# 1.net
KiCad netlist of a schematic drawn in Altium Designer
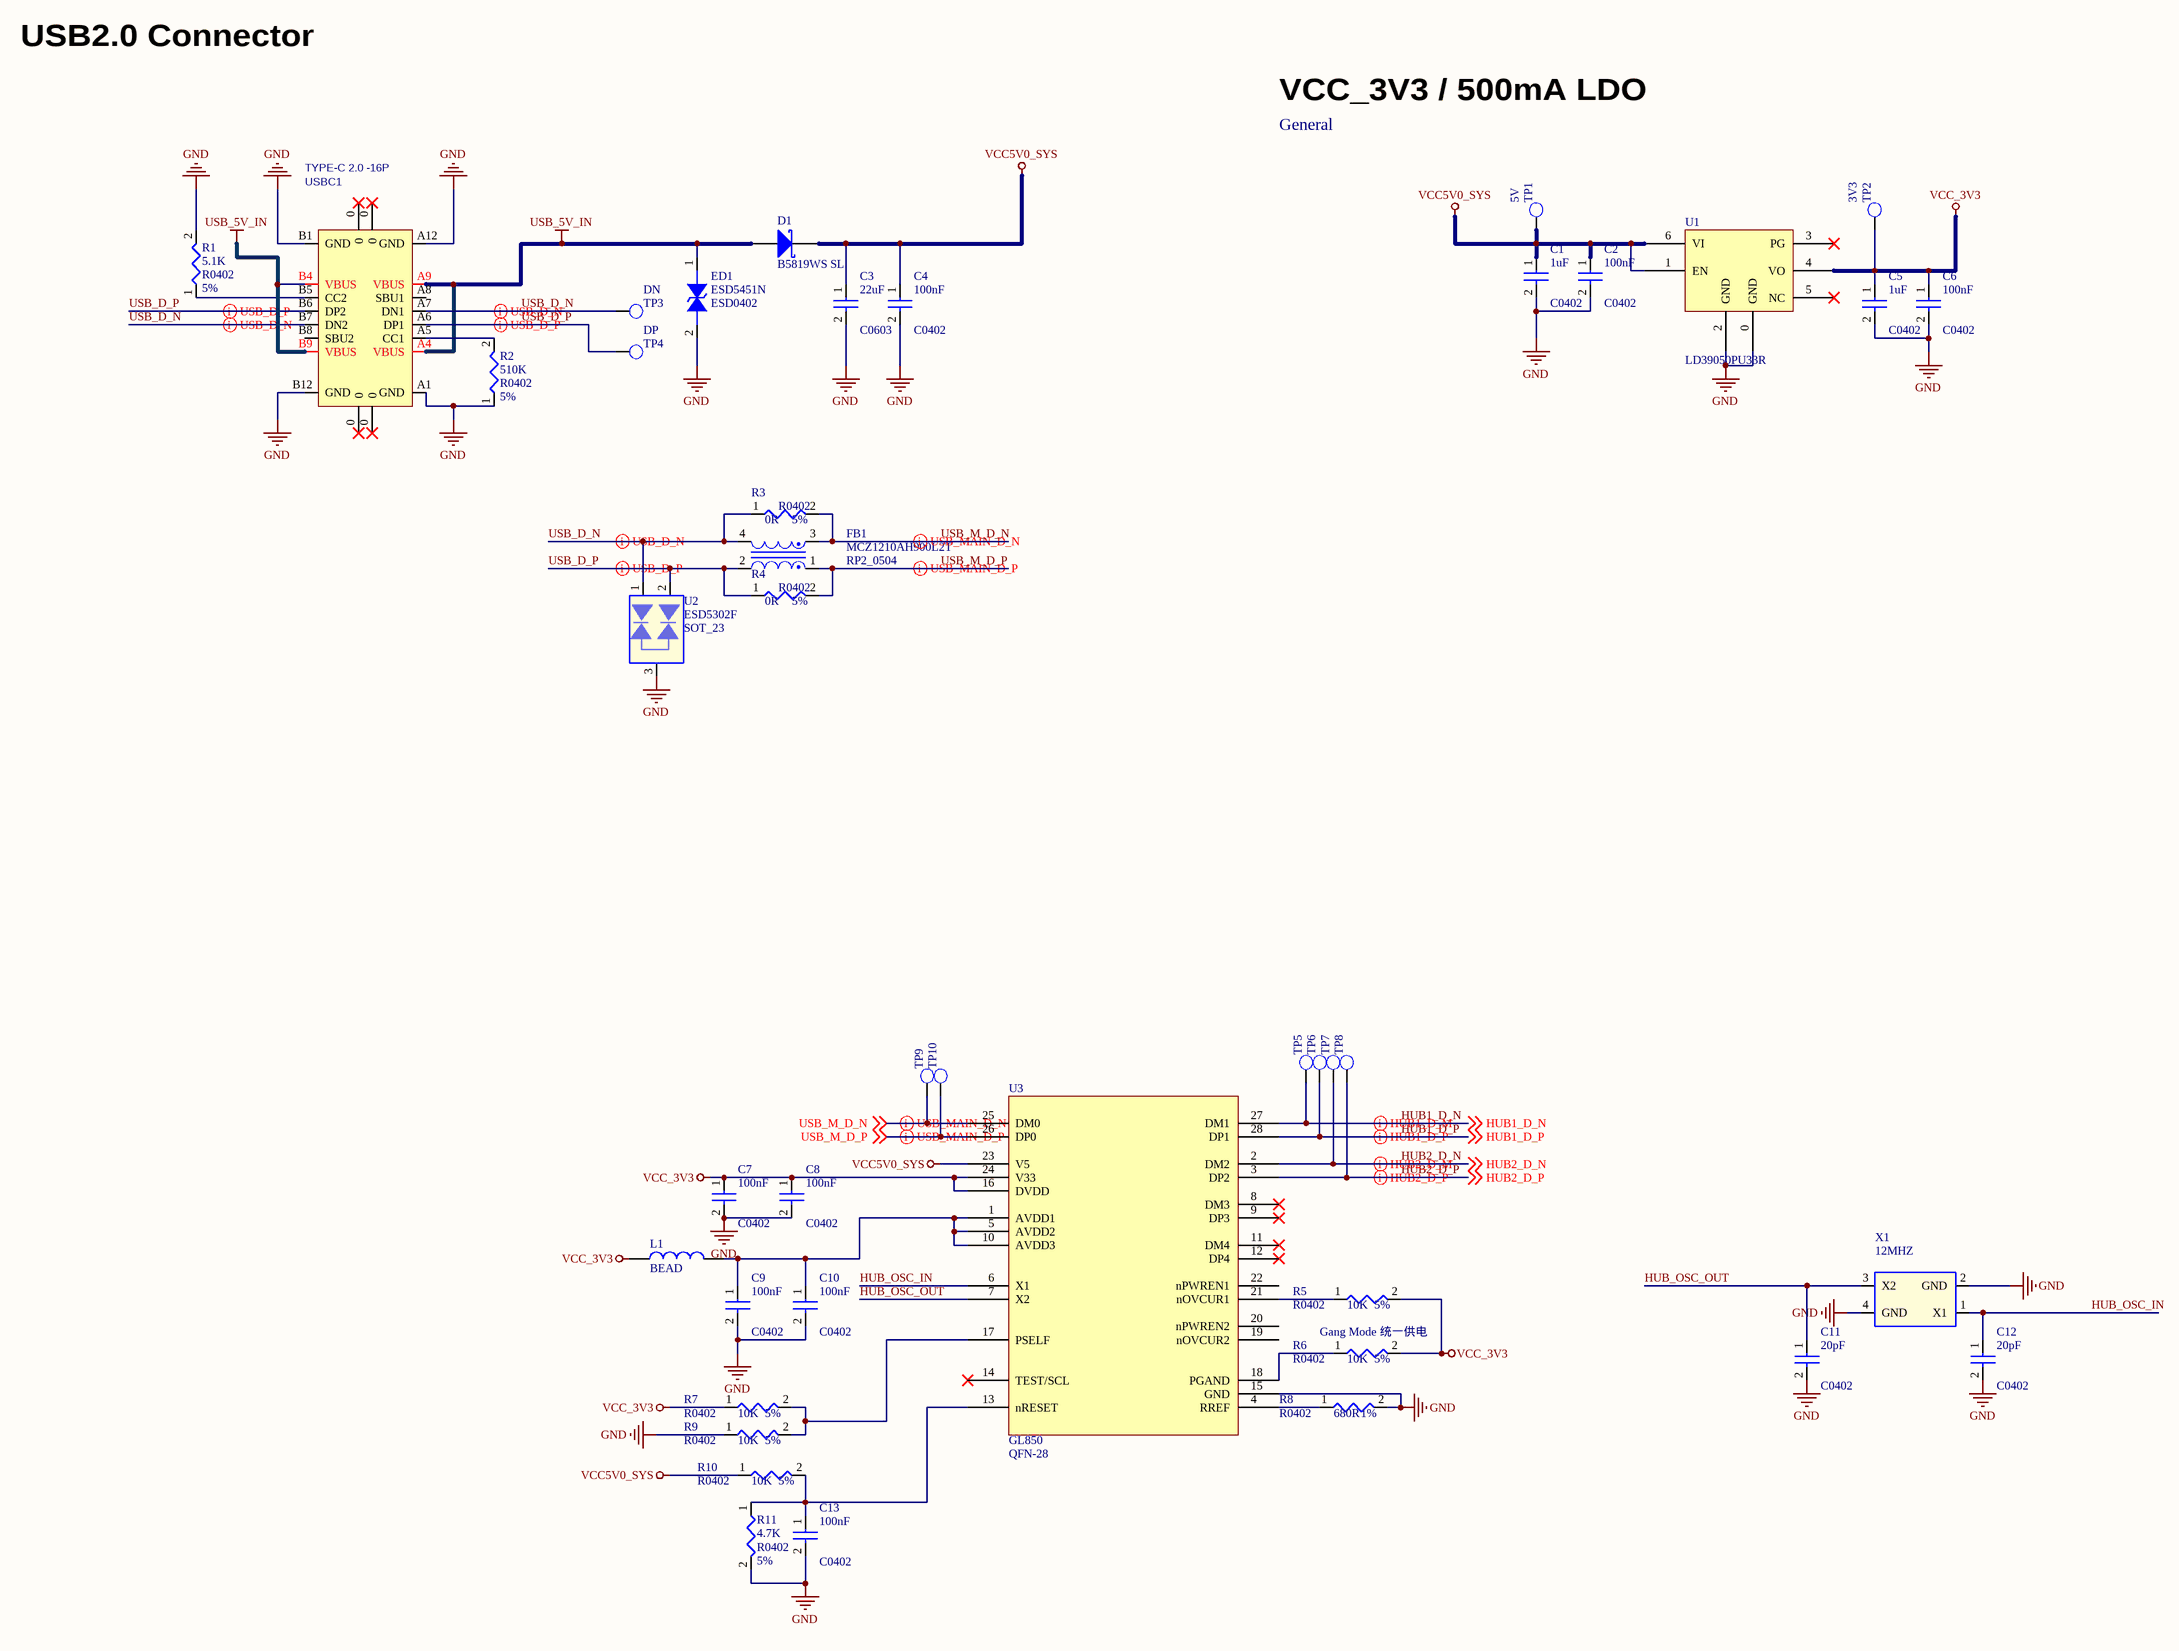
[diagram p0: 1.SchDoc]

(export (version "E")
  (design (tool "Eeschema 10.0.6"))
  (components
    (comp (ref "C1")
      (value "1uF")
      (footprint "C0402_L")
      (description "cap,1.0uF,+/-10%,6.3V,X5R,C0402")
      (fields (field (name "PCB FOOTPRINT") "C0402") (field (name "MANUFACTURER_PART_NUMBER") "Open/Any"))
      (libsource (lib "*") (part "CAP NP_Dup1"))
    )
    (comp (ref "C2")
      (value "100nF")
      (footprint "C0402_L")
      (description "cap,1.0uF,+/-10%,6.3V,C0402")
      (fields (field (name "PCB FOOTPRINT") "C0402") (field (name "MANUFACTURER_PART_NUMBER") "Open/Any"))
      (libsource (lib "*") (part "CAP NP_Dup1"))
    )
    (comp (ref "C3")
      (value "22uF")
      (footprint "C0603_L")
      (description "cap,22.00uF,+/-10%,10V,X5R,C0603")
      (fields (field (name "PCB FOOTPRINT") "C0603") (field (name "MANUFACTURER_PART_NUMBER") "Open/Any"))
      (libsource (lib "*") (part "CAP NP_Dup1"))
    )
    (comp (ref "C4")
      (value "100nF")
      (footprint "C0402_L")
      (description "cap,100.00nF,+/-10%,10V,X5R,C0402")
      (fields (field (name "PCB FOOTPRINT") "C0402") (field (name "MANUFACTURER_PART_NUMBER") "Open/Any"))
      (libsource (lib "*") (part "CAP NP_Dup1"))
    )
    (comp (ref "C5")
      (value "1uF")
      (footprint "C0402_L")
      (description "cap,1.0uF,+/-10%,6.3V,X5R,C0402")
      (fields (field (name "PCB FOOTPRINT") "C0402") (field (name "MANUFACTURER_PART_NUMBER") "Open/Any"))
      (libsource (lib "*") (part "CAP NP_Dup1"))
    )
    (comp (ref "C6")
      (value "100nF")
      (footprint "C0402_L")
      (description "cap,1.0uF,+/-10%,6.3V,C0402")
      (fields (field (name "PCB FOOTPRINT") "C0402") (field (name "MANUFACTURER_PART_NUMBER") "Open/Any"))
      (libsource (lib "*") (part "CAP NP_Dup1"))
    )
    (comp (ref "C7")
      (value "100nF")
      (footprint "C0402_L")
      (description "cap,100.00nF,+/-10%,10V,X5R,C0402")
      (fields (field (name "PCB FOOTPRINT") "C0402") (field (name "MANUFACTURER_PART_NUMBER") "Open/Any"))
      (libsource (lib "*") (part "CAP NP_Dup1"))
    )
    (comp (ref "C8")
      (value "100nF")
      (footprint "C0402_L")
      (description "cap,100.00nF,+/-10%,10V,X5R,C0402")
      (fields (field (name "PCB FOOTPRINT") "C0402") (field (name "MANUFACTURER_PART_NUMBER") "Open/Any"))
      (libsource (lib "*") (part "CAP NP_Dup1"))
    )
    (comp (ref "C9")
      (value "100nF")
      (footprint "C0402_L")
      (description "cap,100.00nF,+/-10%,10V,X5R,C0402")
      (fields (field (name "PCB FOOTPRINT") "C0402") (field (name "MANUFACTURER_PART_NUMBER") "Open/Any"))
      (libsource (lib "*") (part "CAP NP_Dup1"))
    )
    (comp (ref "C10")
      (value "100nF")
      (footprint "C0402_L")
      (description "cap,100.00nF,+/-10%,10V,X5R,C0402")
      (fields (field (name "PCB FOOTPRINT") "C0402") (field (name "MANUFACTURER_PART_NUMBER") "Open/Any"))
      (libsource (lib "*") (part "CAP NP_Dup1"))
    )
    (comp (ref "C11")
      (value "20pF")
      (footprint "C0402_L")
      (description "cap,20pF,+/-10%,25V,X5R,C0402")
      (fields (field (name "PCB FOOTPRINT") "C0402") (field (name "MANUFACTURER_PART_NUMBER") "Open/Any"))
      (libsource (lib "*") (part "CAP NP_Dup1"))
    )
    (comp (ref "C12")
      (value "20pF")
      (footprint "C0402_L")
      (description "cap,20pF,+/-10%,25V,X5R,C0402")
      (fields (field (name "PCB FOOTPRINT") "C0402") (field (name "MANUFACTURER_PART_NUMBER") "Open/Any"))
      (libsource (lib "*") (part "CAP NP_Dup1"))
    )
    (comp (ref "C13")
      (value "100nF")
      (footprint "C0402_L")
      (description "cap,100.00nF,+/-10%,10V,X5R,C0402")
      (fields (field (name "PCB FOOTPRINT") "C0402") (field (name "MANUFACTURER_PART_NUMBER") "Open/Any"))
      (libsource (lib "*") (part "CAP NP_Dup1"))
    )
    (comp (ref "D1")
      (value "B5819WS SL")
      (footprint "SOD-323")
      (description "B5819WS SL 肖特基二极管\r\nSOD-323")
      (libsource (lib "0.2 - 二极管-TVS-ESD-整流桥") (part "SS14"))
    )
    (comp (ref "ED1")
      (value "ESD5451N")
      (footprint "ESD0402")
      (description "1-Line, Bi-directional, Transient Voltage Suppressors.17.5pF.")
      (fields (field (name "PCB FOOTPRINT") "ESD0402"))
      (libsource (lib "*") (part "DIODE BI_DIR TRIG"))
    )
    (comp (ref "FB1")
      (value "MCZ1210AH900L2T")
      (footprint "L0402D")
      (description "MCZ1210AH900L2T, 0603 90Ohm 100MHz")
      (fields (field (name "PCB FOOTPRINT") "RP2_0504"))
      (libsource (lib "*") (part "INDUCTOR COM"))
    )
    (comp (ref "L1")
      (value "BEAD")
      (footprint "L0402")
      (description "鐵氧體磁珠 33ohm 0.55A 550mOhms 0402 Chip Bead")
      (fields (field (name "MANUFACTURER_PART_NUMBER") "MPZ0402S330CTF0W"))
      (libsource (lib "0.1 - 电阻-电容-电感-晶振-晶体-磁珠-电位器") (part "L-AL"))
    )
    (comp (ref "R1")
      (value "5.1K")
      (footprint "R0402")
      (description "通用厚膜电阻,5.1K,+/-5%,R0402")
      (fields
        (field (name "PCB FOOTPRINT") "R0402")
        (field (name "TOLERANCE") "5%")
        (field (name "MANUFACTURER_PART_NUMBER") "Open/Any")
      )
      (libsource (lib "*") (part "RESISTOR"))
    )
    (comp (ref "R2")
      (value "510K")
      (footprint "R0402")
      (description "通用厚膜电阻,510K,+/-1%,R0402")
      (fields
        (field (name "PCB FOOTPRINT") "R0402")
        (field (name "TOLERANCE") "5%")
        (field (name "MANUFACTURER_PART_NUMBER") "Open/Any")
      )
      (libsource (lib "*") (part "RESISTOR"))
    )
    (comp (ref "R3")
      (value "0R")
      (footprint "R0402")
      (description "通用厚膜电阻,0R,+/-5%,R0402")
      (fields
        (field (name "PCB FOOTPRINT") "R0402")
        (field (name "TOLERANCE") "5%")
        (field (name "MANUFACTURER_PART_NUMBER") "Open/Any")
      )
      (libsource (lib "*") (part "RESISTOR"))
    )
    (comp (ref "R4")
      (value "0R")
      (footprint "R0402")
      (description "通用厚膜电阻,0R,+/-5%,R0402")
      (fields
        (field (name "PCB FOOTPRINT") "R0402")
        (field (name "TOLERANCE") "5%")
        (field (name "MANUFACTURER_PART_NUMBER") "Open/Any")
      )
      (libsource (lib "*") (part "RESISTOR"))
    )
    (comp (ref "R5")
      (value "10K")
      (footprint "R0402")
      (description "通用厚膜电阻,10K,+/-5%,R0402")
      (fields
        (field (name "PCB FOOTPRINT") "R0402")
        (field (name "TOLERANCE") "5%")
        (field (name "MANUFACTURER_PART_NUMBER") "Open/Any")
      )
      (libsource (lib "*") (part "RESISTOR"))
    )
    (comp (ref "R6")
      (value "10K")
      (footprint "R0402")
      (description "通用厚膜电阻,10K,+/-5%,R0402")
      (fields
        (field (name "PCB FOOTPRINT") "R0402")
        (field (name "TOLERANCE") "5%")
        (field (name "MANUFACTURER_PART_NUMBER") "Open/Any")
      )
      (libsource (lib "*") (part "RESISTOR"))
    )
    (comp (ref "R7")
      (value "10K")
      (footprint "R0402")
      (description "通用厚膜电阻,10K,+/-5%,R0402")
      (fields
        (field (name "PCB FOOTPRINT") "R0402")
        (field (name "TOLERANCE") "5%")
        (field (name "MANUFACTURER_PART_NUMBER") "Open/Any")
      )
      (libsource (lib "*") (part "RESISTOR"))
    )
    (comp (ref "R8")
      (value "680R")
      (footprint "R0402")
      (description "通用厚膜电阻,680R,+/-1%,R0402")
      (fields
        (field (name "PCB FOOTPRINT") "R0402")
        (field (name "TOLERANCE") "1%")
        (field (name "MANUFACTURER_PART_NUMBER") "Open/Any")
      )
      (libsource (lib "*") (part "RESISTOR"))
    )
    (comp (ref "R9")
      (value "10K")
      (footprint "R0402")
      (description "通用厚膜电阻,10K,+/-5%,R0402")
      (fields
        (field (name "PCB FOOTPRINT") "R0402")
        (field (name "TOLERANCE") "5%")
        (field (name "MANUFACTURER_PART_NUMBER") "Open/Any")
      )
      (libsource (lib "*") (part "RESISTOR"))
    )
    (comp (ref "R10")
      (value "10K")
      (footprint "R0402")
      (description "通用厚膜电阻,10K,+/-5%,R0402")
      (fields
        (field (name "PCB FOOTPRINT") "R0402")
        (field (name "TOLERANCE") "5%")
        (field (name "MANUFACTURER_PART_NUMBER") "Open/Any")
      )
      (libsource (lib "*") (part "RESISTOR"))
    )
    (comp (ref "R11")
      (value "4.7K")
      (footprint "R0402")
      (description "通用厚膜电阻,4.7K,+/-5%,R0402")
      (fields
        (field (name "PCB FOOTPRINT") "R0402")
        (field (name "TOLERANCE") "5%")
        (field (name "MANUFACTURER_PART_NUMBER") "Open/Any")
      )
      (libsource (lib "*") (part "RESISTOR"))
    )
    (comp (ref "TP1")
      (value "5V")
      (footprint "TP_0R70")
      (description "Test Point 0.7mm")
      (libsource (lib "Schlib1") (part "TP"))
    )
    (comp (ref "TP2")
      (value "3V3")
      (footprint "TP_0R70")
      (description "Test Point 0.7mm")
      (libsource (lib "Schlib1") (part "TP"))
    )
    (comp (ref "TP3")
      (value "DN")
      (footprint "TP_0R70")
      (description "Test Point 0.7mm")
      (libsource (lib "Schlib1") (part "TP"))
    )
    (comp (ref "TP4")
      (value "DP")
      (footprint "TP_0R70")
      (description "Test Point 0.7mm")
      (libsource (lib "Schlib1") (part "TP"))
    )
    (comp (ref "TP5")
      (value "~")
      (footprint "TP_0R70")
      (description "Test Point 0.7mm")
      (libsource (lib "Schlib1") (part "TP"))
    )
    (comp (ref "TP6")
      (value "~")
      (footprint "TP_0R70")
      (description "Test Point 0.7mm")
      (libsource (lib "Schlib1") (part "TP"))
    )
    (comp (ref "TP7")
      (value "~")
      (footprint "TP_0R70")
      (description "Test Point 0.7mm")
      (libsource (lib "Schlib1") (part "TP"))
    )
    (comp (ref "TP8")
      (value "~")
      (footprint "TP_0R70")
      (description "Test Point 0.7mm")
      (libsource (lib "Schlib1") (part "TP"))
    )
    (comp (ref "TP9")
      (value "~")
      (footprint "TP_0R70")
      (description "Test Point 0.7mm")
      (libsource (lib "Schlib1") (part "TP"))
    )
    (comp (ref "TP10")
      (value "~")
      (footprint "TP_0R70")
      (description "Test Point 0.7mm")
      (libsource (lib "Schlib1") (part "TP"))
    )
    (comp (ref "U1")
      (value "LD39050PU33R")
      (footprint "SON95P300X300X100-7N")
      (description "LD39050PU33R \r\n 6-DFN (3x3)\r\nOutput 500mA")
      (libsource (lib "Schlib1") (part "LD39050PU33R"))
    )
    (comp (ref "U2")
      (value "ESD5302F")
      (footprint "SOT23")
      (description "2-Lines, Uni-directional,Ultra-low Capacitance.Transient Voltage Suppressors")
      (fields (field (name "PCB FOOTPRINT") "SOT_23"))
      (libsource (lib "*") (part "ESD_ESDA6V8UL"))
    )
    (comp (ref "U3")
      (value "GL850")
      (footprint "QFN-28")
      (description "GL850 4 Port USB HUB QFN-28")
      (fields (field (name "PACKAGE") "QFN-28") (field (name "MANUFACTURER_PART_NUMBER") "GL850G-OHYXX"))
      (libsource (lib "Schlib1") (part "GL850G"))
    )
    (comp (ref "USBC1")
      (value "TYPE-C 2.0 -16P")
      (footprint "USB-C-SMD_16P")
      (description "USB2.0_Type-C_16Pin母座")
      (fields (field (name "MANUFACTURER_PART_NUMBER") "MCCF-R1N1/USB4105-15-A-120"))
      (libsource (lib "0.6 - 电源-以太网-音频-Type-C USB插座") (part "USB2.0_Type-C_16Pin"))
    )
    (comp (ref "X1")
      (value "12MHZ")
      (footprint "XTAL_3225")
      (description "12MHZ (16pF), 3.2 mm x 2.5 mm\r\n无源晶振(谐振器）")
      (fields (field (name "MANUFACTURER_PART_NUMBER") "Open/Any"))
      (libsource (lib "*") (part "CRYSTAL_4P"))
    )
  )
  (nets
    (net (code "1") (name "/HUB_OSC_IN") (class "Default")
      (node (ref "C12") (pin "1") (pinfunction "1_1") (pintype "passive"))
      (node (ref "U3") (pin "6") (pinfunction "X1_6") (pintype "passive"))
      (node (ref "X1") (pin "1") (pinfunction "X1_1") (pintype "passive"))
    )
    (net (code "2") (name "/HUB_OSC_OUT") (class "Default")
      (node (ref "C11") (pin "1") (pinfunction "1_1") (pintype "passive"))
      (node (ref "U3") (pin "7") (pinfunction "X2_7") (pintype "passive"))
      (node (ref "X1") (pin "3") (pinfunction "X2_3") (pintype "passive"))
    )
    (net (code "3") (name "/USB_D_N") (class "Default")
      (node (ref "FB1") (pin "4") (pinfunction "4_4") (pintype "passive"))
      (node (ref "R3") (pin "1") (pinfunction "1_1") (pintype "passive"))
      (node (ref "TP3") (pin "1") (pinfunction "1_1") (pintype "passive"))
      (node (ref "U2") (pin "1") (pinfunction "1_1") (pintype "passive"))
      (node (ref "USBC1") (pin "A7") (pinfunction "DN1_A7") (pintype "passive"))
      (node (ref "USBC1") (pin "B7") (pinfunction "DN2_B7") (pintype "passive"))
    )
    (net (code "4") (name "/USB_D_P") (class "Default")
      (node (ref "FB1") (pin "2") (pinfunction "2_2") (pintype "passive"))
      (node (ref "R4") (pin "1") (pinfunction "1_1") (pintype "passive"))
      (node (ref "TP4") (pin "1") (pinfunction "1_1") (pintype "passive"))
      (node (ref "U2") (pin "2") (pinfunction "2_2") (pintype "passive"))
      (node (ref "USBC1") (pin "A6") (pinfunction "DP1_A6") (pintype "passive"))
      (node (ref "USBC1") (pin "B6") (pinfunction "DP2_B6") (pintype "passive"))
    )
    (net (code "5") (name "GND") (class "Default")
      (node (ref "C1") (pin "2") (pinfunction "2_2") (pintype "passive"))
      (node (ref "C10") (pin "2") (pinfunction "2_2") (pintype "passive"))
      (node (ref "C11") (pin "2") (pinfunction "2_2") (pintype "passive"))
      (node (ref "C12") (pin "2") (pinfunction "2_2") (pintype "passive"))
      (node (ref "C13") (pin "2") (pinfunction "2_2") (pintype "passive"))
      (node (ref "C2") (pin "2") (pinfunction "2_2") (pintype "passive"))
      (node (ref "C3") (pin "2") (pinfunction "2_2") (pintype "passive"))
      (node (ref "C4") (pin "2") (pinfunction "2_2") (pintype "passive"))
      (node (ref "C5") (pin "2") (pinfunction "2_2") (pintype "passive"))
      (node (ref "C6") (pin "2") (pinfunction "2_2") (pintype "passive"))
      (node (ref "C7") (pin "2") (pinfunction "2_2") (pintype "passive"))
      (node (ref "C8") (pin "2") (pinfunction "2_2") (pintype "passive"))
      (node (ref "C9") (pin "2") (pinfunction "2_2") (pintype "passive"))
      (node (ref "ED1") (pin "2") (pinfunction "2_2") (pintype "passive"))
      (node (ref "R1") (pin "2") (pinfunction "2_2") (pintype "passive"))
      (node (ref "R11") (pin "2") (pinfunction "2_2") (pintype "passive"))
      (node (ref "R2") (pin "1") (pinfunction "1_1") (pintype "passive"))
      (node (ref "R8") (pin "2") (pinfunction "2_2") (pintype "passive"))
      (node (ref "R9") (pin "1") (pinfunction "1_1") (pintype "passive"))
      (node (ref "U1") (pin "0") (pinfunction "GND_0") (pintype "passive"))
      (node (ref "U1") (pin "2") (pinfunction "GND_2") (pintype "passive"))
      (node (ref "U2") (pin "3") (pinfunction "3_3") (pintype "passive"))
      (node (ref "U3") (pin "15") (pinfunction "GND_15") (pintype "passive"))
      (node (ref "USBC1") (pin "A1") (pinfunction "GND_A1") (pintype "passive"))
      (node (ref "USBC1") (pin "A12") (pinfunction "GND_A12") (pintype "passive"))
      (node (ref "USBC1") (pin "B1") (pinfunction "GND_B1") (pintype "passive"))
      (node (ref "USBC1") (pin "B12") (pinfunction "GND_B12") (pintype "passive"))
      (node (ref "X1") (pin "2") (pinfunction "GND_2") (pintype "power_in"))
      (node (ref "X1") (pin "4") (pinfunction "GND_4") (pintype "power_in"))
    )
    (net (code "6") (name "HUB1_D_N") (class "Default")
      (node (ref "TP5") (pin "1") (pinfunction "1_1") (pintype "passive"))
      (node (ref "U3") (pin "27") (pinfunction "DM1_27") (pintype "passive"))
    )
    (net (code "7") (name "HUB1_D_P") (class "Default")
      (node (ref "TP6") (pin "1") (pinfunction "1_1") (pintype "passive"))
      (node (ref "U3") (pin "28") (pinfunction "DP1_28") (pintype "passive"))
    )
    (net (code "8") (name "HUB2_D_N") (class "Default")
      (node (ref "TP7") (pin "1") (pinfunction "1_1") (pintype "passive"))
      (node (ref "U3") (pin "2") (pinfunction "DM2_2") (pintype "passive"))
    )
    (net (code "9") (name "HUB2_D_P") (class "Default")
      (node (ref "TP8") (pin "1") (pinfunction "1_1") (pintype "passive"))
      (node (ref "U3") (pin "3") (pinfunction "DP2_3") (pintype "passive"))
    )
    (net (code "10") (name "Net-(U3-AVDD1)") (class "Default")
      (node (ref "C10") (pin "1") (pinfunction "1_1") (pintype "passive"))
      (node (ref "C9") (pin "1") (pinfunction "1_1") (pintype "passive"))
      (node (ref "L1") (pin "2") (pinfunction "2_2") (pintype "passive"))
      (node (ref "U3") (pin "1") (pinfunction "AVDD1_1") (pintype "passive"))
      (node (ref "U3") (pin "10") (pinfunction "AVDD3_10") (pintype "passive"))
      (node (ref "U3") (pin "5") (pinfunction "AVDD2_5") (pintype "passive"))
    )
    (net (code "11") (name "Net-(U3-PGAND)") (class "Default")
      (node (ref "R6") (pin "1") (pinfunction "1_1") (pintype "passive"))
      (node (ref "U3") (pin "18") (pinfunction "PGAND_18") (pintype "passive"))
    )
    (net (code "12") (name "Net-(U3-PSELF)") (class "Default")
      (node (ref "R7") (pin "2") (pinfunction "2_2") (pintype "passive"))
      (node (ref "R9") (pin "2") (pinfunction "2_2") (pintype "passive"))
      (node (ref "U3") (pin "17") (pinfunction "PSELF_17") (pintype "passive"))
    )
    (net (code "13") (name "Net-(U3-RREF)") (class "Default")
      (node (ref "R8") (pin "1") (pinfunction "1_1") (pintype "passive"))
      (node (ref "U3") (pin "4") (pinfunction "RREF_4") (pintype "passive"))
    )
    (net (code "14") (name "Net-(U3-nOVCUR1)") (class "Default")
      (node (ref "R5") (pin "1") (pinfunction "1_1") (pintype "passive"))
      (node (ref "U3") (pin "21") (pinfunction "nOVCUR1_21") (pintype "passive"))
    )
    (net (code "15") (name "Net-(U3-nRESET)") (class "Default")
      (node (ref "C13") (pin "1") (pinfunction "1_1") (pintype "passive"))
      (node (ref "R10") (pin "2") (pinfunction "2_2") (pintype "passive"))
      (node (ref "R11") (pin "1") (pinfunction "1_1") (pintype "passive"))
      (node (ref "U3") (pin "13") (pinfunction "nRESET_13") (pintype "passive"))
    )
    (net (code "16") (name "Net-(USBC1-CC1)") (class "Default")
      (node (ref "R2") (pin "2") (pinfunction "2_2") (pintype "passive"))
      (node (ref "USBC1") (pin "A5") (pinfunction "CC1_A5") (pintype "passive"))
    )
    (net (code "17") (name "Net-(USBC1-CC2)") (class "Default")
      (node (ref "R1") (pin "1") (pinfunction "1_1") (pintype "passive"))
      (node (ref "USBC1") (pin "B5") (pinfunction "CC2_B5") (pintype "passive"))
    )
    (net (code "18") (name "USB_5V_IN") (class "Default")
      (node (ref "D1") (pin "1") (pinfunction "A_1") (pintype "passive"))
      (node (ref "ED1") (pin "1") (pinfunction "1_1") (pintype "passive"))
      (node (ref "USBC1") (pin "A4") (pinfunction "VBUS_A4") (pintype "passive"))
      (node (ref "USBC1") (pin "A9") (pinfunction "VBUS_A9") (pintype "passive"))
      (node (ref "USBC1") (pin "B4") (pinfunction "VBUS_B4") (pintype "passive"))
      (node (ref "USBC1") (pin "B9") (pinfunction "VBUS_B9") (pintype "passive"))
    )
    (net (code "19") (name "USB_M_D_N") (class "Default")
      (node (ref "FB1") (pin "3") (pinfunction "3_3") (pintype "passive"))
      (node (ref "R3") (pin "2") (pinfunction "2_2") (pintype "passive"))
      (node (ref "TP9") (pin "1") (pinfunction "1_1") (pintype "passive"))
      (node (ref "U3") (pin "25") (pinfunction "DM0_25") (pintype "passive"))
    )
    (net (code "20") (name "USB_M_D_P") (class "Default")
      (node (ref "FB1") (pin "1") (pinfunction "1_1") (pintype "passive"))
      (node (ref "R4") (pin "2") (pinfunction "2_2") (pintype "passive"))
      (node (ref "TP10") (pin "1") (pinfunction "1_1") (pintype "passive"))
      (node (ref "U3") (pin "26") (pinfunction "DP0_26") (pintype "passive"))
    )
    (net (code "21") (name "VCC5V0_SYS") (class "Default")
      (node (ref "C1") (pin "1") (pinfunction "1_1") (pintype "passive"))
      (node (ref "C2") (pin "1") (pinfunction "1_1") (pintype "passive"))
      (node (ref "C3") (pin "1") (pinfunction "1_1") (pintype "passive"))
      (node (ref "C4") (pin "1") (pinfunction "1_1") (pintype "passive"))
      (node (ref "D1") (pin "2") (pinfunction "K_2") (pintype "passive"))
      (node (ref "R10") (pin "1") (pinfunction "1_1") (pintype "passive"))
      (node (ref "TP1") (pin "1") (pinfunction "1_1") (pintype "passive"))
      (node (ref "U1") (pin "1") (pinfunction "EN_1") (pintype "passive"))
      (node (ref "U1") (pin "6") (pinfunction "VI_6") (pintype "passive"))
      (node (ref "U3") (pin "23") (pinfunction "V5_23") (pintype "passive"))
    )
    (net (code "22") (name "VCC_3V3") (class "Default")
      (node (ref "C5") (pin "1") (pinfunction "1_1") (pintype "passive"))
      (node (ref "C6") (pin "1") (pinfunction "1_1") (pintype "passive"))
      (node (ref "C7") (pin "1") (pinfunction "1_1") (pintype "passive"))
      (node (ref "C8") (pin "1") (pinfunction "1_1") (pintype "passive"))
      (node (ref "L1") (pin "1") (pinfunction "1_1") (pintype "passive"))
      (node (ref "R5") (pin "2") (pinfunction "2_2") (pintype "passive"))
      (node (ref "R6") (pin "2") (pinfunction "2_2") (pintype "passive"))
      (node (ref "R7") (pin "1") (pinfunction "1_1") (pintype "passive"))
      (node (ref "TP2") (pin "1") (pinfunction "1_1") (pintype "passive"))
      (node (ref "U1") (pin "4") (pinfunction "VO_4") (pintype "passive"))
      (node (ref "U3") (pin "16") (pinfunction "DVDD_16") (pintype "passive"))
      (node (ref "U3") (pin "24") (pinfunction "V33_24") (pintype "passive"))
    )
    (net (code "23") (name "unconnected-(U1-NC-Pad5)") (class "Default")
      (node (ref "U1") (pin "5") (pinfunction "NC_5") (pintype "passive+no_connect"))
    )
    (net (code "24") (name "unconnected-(U1-PG-Pad3)") (class "Default")
      (node (ref "U1") (pin "3") (pinfunction "PG_3") (pintype "passive+no_connect"))
    )
    (net (code "25") (name "unconnected-(U3-DM3-Pad8)") (class "Default")
      (node (ref "U3") (pin "8") (pinfunction "DM3_8") (pintype "passive+no_connect"))
    )
    (net (code "26") (name "unconnected-(U3-DM4-Pad11)") (class "Default")
      (node (ref "U3") (pin "11") (pinfunction "DM4_11") (pintype "passive+no_connect"))
    )
    (net (code "27") (name "unconnected-(U3-DP3-Pad9)") (class "Default")
      (node (ref "U3") (pin "9") (pinfunction "DP3_9") (pintype "passive+no_connect"))
    )
    (net (code "28") (name "unconnected-(U3-DP4-Pad12)") (class "Default")
      (node (ref "U3") (pin "12") (pinfunction "DP4_12") (pintype "passive+no_connect"))
    )
    (net (code "29") (name "unconnected-(U3-TEST{slash}SCL-Pad14)") (class "Default")
      (node (ref "U3") (pin "14") (pinfunction "TEST/SCL_14") (pintype "passive+no_connect"))
    )
    (net (code "30") (name "unconnected-(U3-nOVCUR2-Pad19)") (class "Default")
      (node (ref "U3") (pin "19") (pinfunction "nOVCUR2_19") (pintype "passive"))
    )
    (net (code "31") (name "unconnected-(U3-nPWREN1-Pad22)") (class "Default")
      (node (ref "U3") (pin "22") (pinfunction "nPWREN1_22") (pintype "passive"))
    )
    (net (code "32") (name "unconnected-(U3-nPWREN2-Pad20)") (class "Default")
      (node (ref "U3") (pin "20") (pinfunction "nPWREN2_20") (pintype "passive"))
    )
    (net (code "33") (name "unconnected-(USBC1-Pad0)") (class "Default")
      (node (ref "USBC1") (pin "0") (pinfunction "0_0") (pintype "passive+no_connect"))
    )
    (net (code "34") (name "unconnected-(USBC1-Pad0)_1") (class "Default")
      (node (ref "USBC1") (pin "0") (pinfunction "0_0") (pintype "passive+no_connect"))
    )
    (net (code "35") (name "unconnected-(USBC1-Pad0)_2") (class "Default")
      (node (ref "USBC1") (pin "0") (pinfunction "0_0") (pintype "passive+no_connect"))
    )
    (net (code "36") (name "unconnected-(USBC1-Pad0)_3") (class "Default")
      (node (ref "USBC1") (pin "0") (pinfunction "0_0") (pintype "passive+no_connect"))
    )
    (net (code "37") (name "unconnected-(USBC1-SBU1-PadA8)") (class "Default")
      (node (ref "USBC1") (pin "A8") (pinfunction "SBU1_A8") (pintype "passive"))
    )
    (net (code "38") (name "unconnected-(USBC1-SBU2-PadB8)") (class "Default")
      (node (ref "USBC1") (pin "B8") (pinfunction "SBU2_B8") (pintype "passive"))
    )
  )
)
